# 500uH.net
KiCad netlist of a schematic drawn in EAGLE
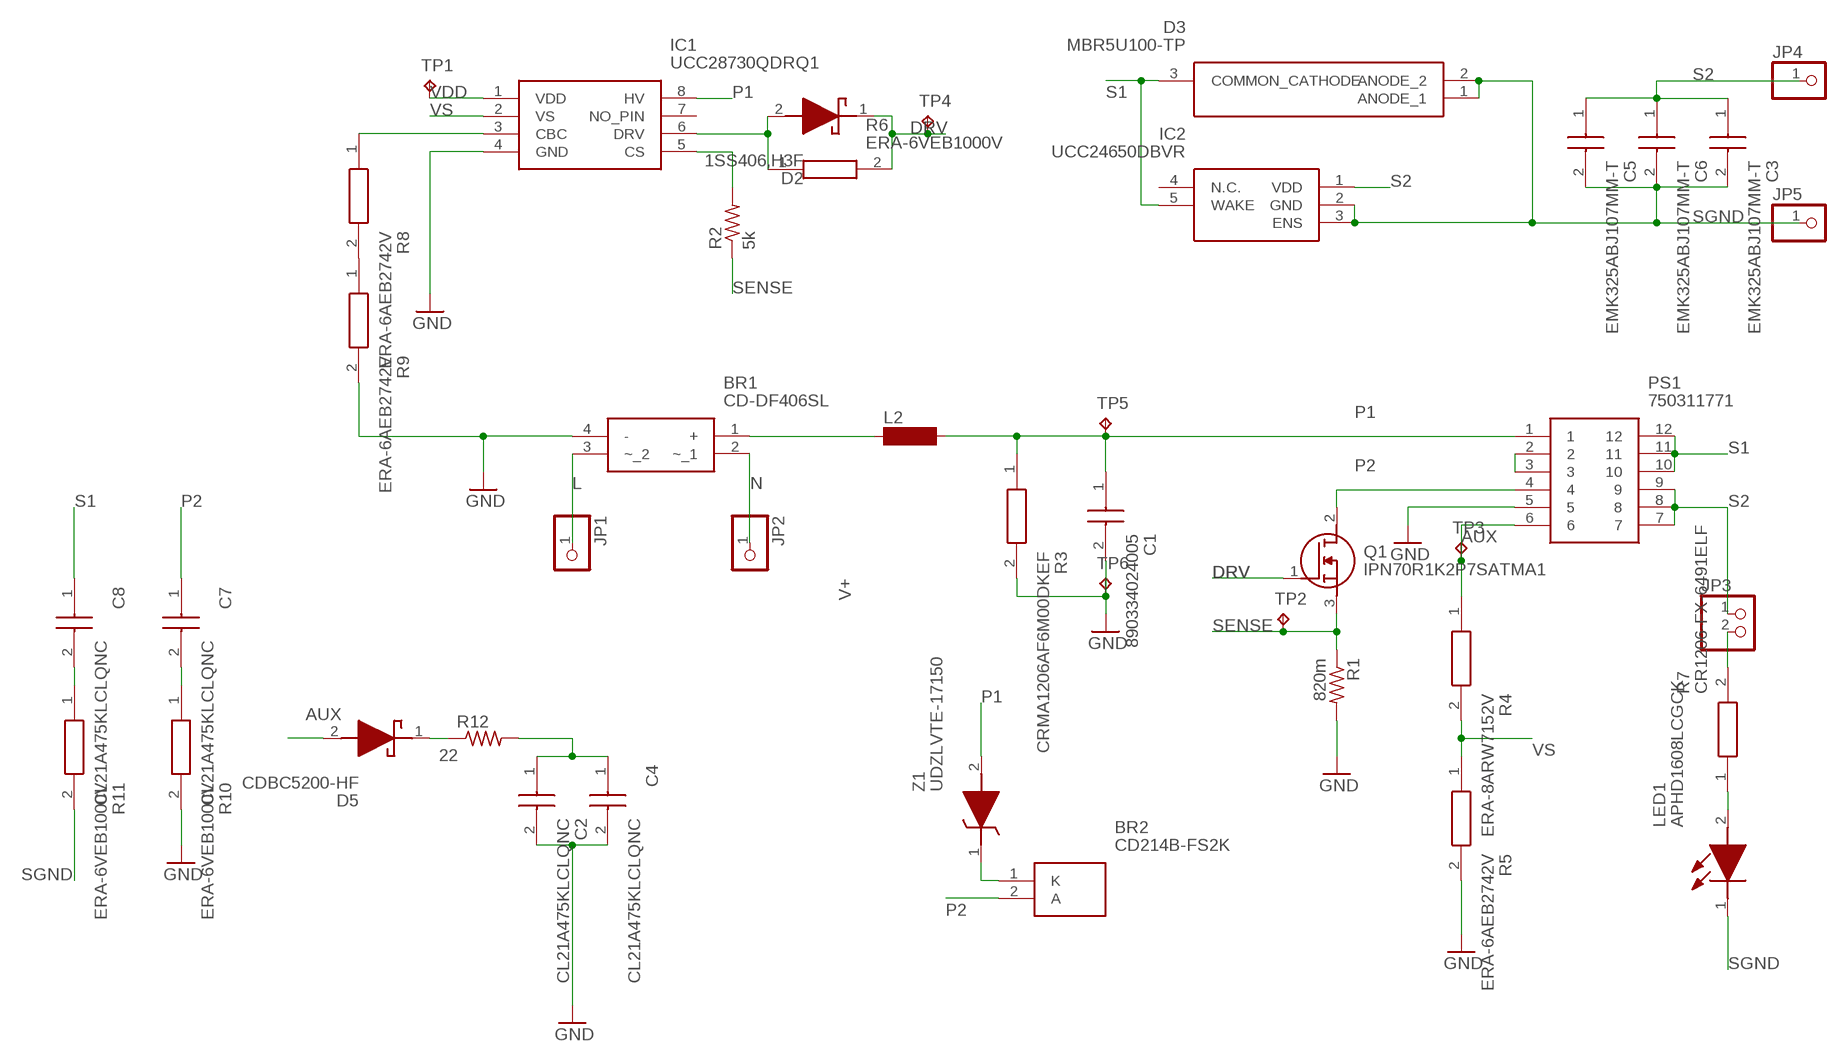
[diagram p0: schematic, sheet 1]

(export (version "E")
  (design (tool "Eeschema 10.0.6"))
  (components
    (comp (ref "BR1")
      (value "CD-DF406SL")
      (footprint "eagle-import:CDDF406SL")
      (fields (field (name "MOUSER_PART_NUMBER") "652-CD-DF406SL"))
      (libsource (lib "eagle-import") (part "CD-DF406SL"))
    )
    (comp (ref "BR2")
      (value "CD214B-FS2K")
      (footprint "eagle-import:CD214BFS2K")
      (fields (field (name "MOUSER_PART_NUMBER") "652-CD214B-FS2K"))
      (libsource (lib "eagle-import") (part "CD214B-FS2K"))
    )
    (comp (ref "C1")
      (value "890334024005")
      (footprint "eagle-import:890334024005")
      (fields (field (name "MOUSER_PART_NUMBER") "710-890334024005"))
      (libsource (lib "eagle-import") (part "890334024005"))
    )
    (comp (ref "C2")
      (value "CL21A475KLCLQNC")
      (footprint "eagle-import:CAPC2012X95N")
      (fields (field (name "MOUSER_PART_NUMBER") "187-CL21A475KLCLQNC"))
      (libsource (lib "eagle-import") (part "CL21A475KLCLQNC"))
    )
    (comp (ref "C3")
      (value "EMK325ABJ107MM-T")
      (footprint "eagle-import:CAPC3225X270N")
      (fields (field (name "MOUSER_PART_NUMBER") "963-EMK325ABJ107MM-T"))
      (libsource (lib "eagle-import") (part "EMK325ABJ107MM-T"))
    )
    (comp (ref "C4")
      (value "CL21A475KLCLQNC")
      (footprint "eagle-import:CAPC2012X95N")
      (fields (field (name "MOUSER_PART_NUMBER") "187-CL21A475KLCLQNC"))
      (libsource (lib "eagle-import") (part "CL21A475KLCLQNC"))
    )
    (comp (ref "C5")
      (value "EMK325ABJ107MM-T")
      (footprint "eagle-import:CAPC3225X270N")
      (fields (field (name "MOUSER_PART_NUMBER") "963-EMK325ABJ107MM-T"))
      (libsource (lib "eagle-import") (part "EMK325ABJ107MM-T"))
    )
    (comp (ref "C6")
      (value "EMK325ABJ107MM-T")
      (footprint "eagle-import:CAPC3225X270N")
      (fields (field (name "MOUSER_PART_NUMBER") "963-EMK325ABJ107MM-T"))
      (libsource (lib "eagle-import") (part "EMK325ABJ107MM-T"))
    )
    (comp (ref "C7")
      (value "CL21A475KLCLQNC")
      (footprint "eagle-import:CAPC2012X95N")
      (fields (field (name "MOUSER_PART_NUMBER") "187-CL21A475KLCLQNC"))
      (libsource (lib "eagle-import") (part "CL21A475KLCLQNC"))
    )
    (comp (ref "C8")
      (value "CL21A475KLCLQNC")
      (footprint "eagle-import:CAPC2012X95N")
      (fields (field (name "MOUSER_PART_NUMBER") "187-CL21A475KLCLQNC"))
      (libsource (lib "eagle-import") (part "CL21A475KLCLQNC"))
    )
    (comp (ref "D2")
      (value "1SS406,H3F")
      (footprint "eagle-import:SOD2513X115N")
      (fields (field (name "MOUSER_PART_NUMBER") "757-1SS406H3F"))
      (libsource (lib "eagle-import") (part "1SS406,H3F"))
    )
    (comp (ref "D3")
      (value "MBR5U100-TP")
      (footprint "eagle-import:MBR5U100TP")
      (libsource (lib "eagle-import") (part "MBR5U100-TP"))
    )
    (comp (ref "D5")
      (value "CDBC5200-HF")
      (footprint "eagle-import:DIOM8059X290N")
      (fields (field (name "MOUSER_PART_NUMBER") "750-CDBC5200-HF"))
      (libsource (lib "eagle-import") (part "CDBC5200-HF"))
    )
    (comp (ref "IC1")
      (value "UCC28730QDRQ1")
      (footprint "eagle-import:SOIC127P600X175-8N")
      (fields (field (name "MOUSER_PART_NUMBER") "595-UCC28730QDRQ1"))
      (libsource (lib "eagle-import") (part "UCC28730QDRQ1"))
    )
    (comp (ref "IC2")
      (value "UCC24650DBVR")
      (footprint "eagle-import:SOT95P280X145-5N")
      (fields (field (name "MOUSER_PART_NUMBER") "595-UCC24650DBVR"))
      (libsource (lib "eagle-import") (part "UCC24650DBVR"))
    )
    (comp (ref "JP1")
      (value "PINHD-1X1")
      (footprint "eagle-import:1X01")
      (libsource (lib "eagle-import") (part "PINHD-1X1"))
    )
    (comp (ref "JP2")
      (value "PINHD-1X1")
      (footprint "eagle-import:1X01")
      (libsource (lib "eagle-import") (part "PINHD-1X1"))
    )
    (comp (ref "JP3")
      (value "PINHD-1X2")
      (footprint "eagle-import:1X02")
      (libsource (lib "eagle-import") (part "PINHD-1X2"))
    )
    (comp (ref "JP4")
      (value "PINHD-1X1")
      (footprint "eagle-import:1X01")
      (libsource (lib "eagle-import") (part "PINHD-1X1"))
    )
    (comp (ref "JP5")
      (value "PINHD-1X1")
      (footprint "eagle-import:1X01")
      (libsource (lib "eagle-import") (part "PINHD-1X1"))
    )
    (comp (ref "L2")
      (value "MS50SRU1048-471Y")
      (footprint "eagle-import:INDDFN1000X1000X480-2N")
      (libsource (lib "eagle-import") (part "MS50SRU1048-471Y"))
    )
    (comp (ref "LED1")
      (value "APHD1608LCGCK")
      (footprint "eagle-import:LEDM168X80N")
      (fields (field (name "MOUSER_PART_NUMBER") "604-APHD1608LCGCK"))
      (libsource (lib "eagle-import") (part "APHD1608LCGCK"))
    )
    (comp (ref "PS1")
      (value "750311771")
      (footprint "eagle-import:750311771")
      (fields (field (name "MOUSER_PART_NUMBER") "710-750311771") (field (name "SPICEPREFIX") "X"))
      (libsource (lib "eagle-import") (part "750311771"))
    )
    (comp (ref "Q1")
      (value "IPN70R1K2P7SATMA1")
      (footprint "eagle-import:IPN70R1K2P7SATMA1")
      (fields (field (name "MOUSER_PART_NUMBER") "726-IPN70R1K2P7SATM1"))
      (libsource (lib "eagle-import") (part "IPN70R1K2P7SATMA1"))
    )
    (comp (ref "R1")
      (value "820m")
      (footprint "eagle-import:R0805")
      (libsource (lib "eagle-import") (part "R-US_R0805"))
    )
    (comp (ref "R2")
      (value "5k")
      (footprint "eagle-import:R0805")
      (libsource (lib "eagle-import") (part "R-US_R0805"))
    )
    (comp (ref "R3")
      (value "CRMA1206AF6M00DKEF")
      (footprint "eagle-import:RESC3216X74N")
      (libsource (lib "eagle-import") (part "CRMA1206AF6M00DKEF"))
    )
    (comp (ref "R4")
      (value "ERA-8ARW7152V")
      (footprint "eagle-import:ERA8A_(0805)")
      (fields (field (name "MOUSER_PART_NUMBER") "667-ERA-8ARW7152V"))
      (libsource (lib "eagle-import") (part "ERA-8ARW7152V"))
    )
    (comp (ref "R5")
      (value "ERA-6AEB2742V")
      (footprint "eagle-import:ERA6A_(0805)")
      (fields (field (name "MOUSER_PART_NUMBER") "667-ERA-6AEB2742V"))
      (libsource (lib "eagle-import") (part "ERA-6AEB2742V"))
    )
    (comp (ref "R6")
      (value "ERA-6VEB1000V")
      (footprint "eagle-import:ERA6VK")
      (fields (field (name "MOUSER_PART_NUMBER") "667-ERA-6VEB1000V"))
      (libsource (lib "eagle-import") (part "ERA-6VEB1000V"))
    )
    (comp (ref "R7")
      (value "CR1206-FX-6491ELF")
      (footprint "eagle-import:RESC3216X75N")
      (fields (field (name "MOUSER_PART_NUMBER") "652-CR1206FX-6491ELF"))
      (libsource (lib "eagle-import") (part "CR1206-FX-6491ELF"))
    )
    (comp (ref "R8")
      (value "ERA-6AEB2742V")
      (footprint "eagle-import:ERA6A_(0805)")
      (fields (field (name "MOUSER_PART_NUMBER") "667-ERA-6AEB2742V"))
      (libsource (lib "eagle-import") (part "ERA-6AEB2742V"))
    )
    (comp (ref "R9")
      (value "ERA-6AEB2742V")
      (footprint "eagle-import:ERA6A_(0805)")
      (fields (field (name "MOUSER_PART_NUMBER") "667-ERA-6AEB2742V"))
      (libsource (lib "eagle-import") (part "ERA-6AEB2742V"))
    )
    (comp (ref "R10")
      (value "ERA-6VEB1000V")
      (footprint "eagle-import:ERA6VK")
      (fields (field (name "MOUSER_PART_NUMBER") "667-ERA-6VEB1000V"))
      (libsource (lib "eagle-import") (part "ERA-6VEB1000V"))
    )
    (comp (ref "R11")
      (value "ERA-6VEB1000V")
      (footprint "eagle-import:ERA6VK")
      (fields (field (name "MOUSER_PART_NUMBER") "667-ERA-6VEB1000V"))
      (libsource (lib "eagle-import") (part "ERA-6VEB1000V"))
    )
    (comp (ref "R12")
      (value "22")
      (footprint "eagle-import:R0805")
      (libsource (lib "eagle-import") (part "R-US_R0805"))
    )
    (comp (ref "TP1")
      (value "TPB1,27")
      (footprint "eagle-import:B1,27")
      (libsource (lib "eagle-import") (part "TPB1,27"))
    )
    (comp (ref "TP2")
      (value "TPB1,27")
      (footprint "eagle-import:B1,27")
      (libsource (lib "eagle-import") (part "TPB1,27"))
    )
    (comp (ref "TP3")
      (value "TPB1,27")
      (footprint "eagle-import:B1,27")
      (libsource (lib "eagle-import") (part "TPB1,27"))
    )
    (comp (ref "TP4")
      (value "TPB1,27")
      (footprint "eagle-import:B1,27")
      (libsource (lib "eagle-import") (part "TPB1,27"))
    )
    (comp (ref "TP5")
      (value "TPB1,27")
      (footprint "eagle-import:B1,27")
      (libsource (lib "eagle-import") (part "TPB1,27"))
    )
    (comp (ref "TP6")
      (value "TPB1,27")
      (footprint "eagle-import:B1,27")
      (libsource (lib "eagle-import") (part "TPB1,27"))
    )
    (comp (ref "Z1")
      (value "UDZLVTE-17150")
      (footprint "eagle-import:SODFL2512X90N")
      (fields (field (name "MOUSER_PART_NUMBER") "755-UDZLVTE-17150"))
      (libsource (lib "eagle-import") (part "UDZLVTE-17150"))
    )
  )
  (nets
    (net (code "1") (name "/AUX") (class "Default")
      (node (ref "D5") (pin "2") (pinfunction "A_2") (pintype "bidirectional"))
      (node (ref "PS1") (pin "6") (pinfunction "6_6") (pintype "bidirectional"))
      (node (ref "R4") (pin "1") (pinfunction "1_1") (pintype "bidirectional"))
      (node (ref "TP3") (pin "TP") (pinfunction "TP_TP") (pintype "input"))
    )
    (net (code "2") (name "/DRV") (class "Default")
      (node (ref "D2") (pin "1") (pinfunction "K_1") (pintype "bidirectional"))
      (node (ref "Q1") (pin "1") (pinfunction "G_1") (pintype "bidirectional"))
      (node (ref "R6") (pin "2") (pinfunction "2_2") (pintype "bidirectional"))
      (node (ref "TP4") (pin "TP") (pinfunction "TP_TP") (pintype "input"))
    )
    (net (code "3") (name "/L") (class "Default")
      (node (ref "BR1") (pin "3") (pinfunction "~{_2}_3") (pintype "bidirectional"))
      (node (ref "JP1") (pin "1") (pinfunction "1_1") (pintype "passive"))
    )
    (net (code "4") (name "/N") (class "Default")
      (node (ref "BR1") (pin "2") (pinfunction "~{_1}_2") (pintype "bidirectional"))
      (node (ref "JP2") (pin "1") (pinfunction "1_1") (pintype "passive"))
    )
    (net (code "5") (name "/P1") (class "Default")
      (node (ref "C1") (pin "1") (pinfunction "1_1") (pintype "bidirectional"))
      (node (ref "IC1") (pin "8") (pinfunction "HV_8") (pintype "bidirectional"))
      (node (ref "L2") (pin "2") (pinfunction "2_2") (pintype "passive"))
      (node (ref "PS1") (pin "1") (pinfunction "1_1") (pintype "bidirectional"))
      (node (ref "R3") (pin "1") (pinfunction "1_1") (pintype "bidirectional"))
      (node (ref "TP5") (pin "TP") (pinfunction "TP_TP") (pintype "input"))
      (node (ref "Z1") (pin "2") (pinfunction "A_2") (pintype "bidirectional"))
    )
    (net (code "6") (name "/P2") (class "Default")
      (node (ref "BR2") (pin "2") (pinfunction "A_2") (pintype "bidirectional"))
      (node (ref "C7") (pin "1") (pinfunction "1_1") (pintype "bidirectional"))
      (node (ref "PS1") (pin "4") (pinfunction "4_4") (pintype "bidirectional"))
      (node (ref "Q1") (pin "2") (pinfunction "D_2") (pintype "bidirectional"))
    )
    (net (code "7") (name "/S1") (class "Default")
      (node (ref "C8") (pin "1") (pinfunction "1_1") (pintype "bidirectional"))
      (node (ref "D3") (pin "3") (pinfunction "COMMON_CATHODE_3") (pintype "bidirectional"))
      (node (ref "IC2") (pin "5") (pinfunction "WAKE_5") (pintype "bidirectional"))
      (node (ref "PS1") (pin "10") (pinfunction "10_10") (pintype "bidirectional"))
      (node (ref "PS1") (pin "11") (pinfunction "11_11") (pintype "bidirectional"))
      (node (ref "PS1") (pin "12") (pinfunction "12_12") (pintype "bidirectional"))
    )
    (net (code "8") (name "/S2") (class "Default")
      (node (ref "C3") (pin "1") (pinfunction "1_1") (pintype "bidirectional"))
      (node (ref "C5") (pin "1") (pinfunction "1_1") (pintype "bidirectional"))
      (node (ref "C6") (pin "1") (pinfunction "1_1") (pintype "bidirectional"))
      (node (ref "IC2") (pin "1") (pinfunction "VDD_1") (pintype "bidirectional"))
      (node (ref "JP3") (pin "1") (pinfunction "1_1") (pintype "passive"))
      (node (ref "JP4") (pin "1") (pinfunction "1_1") (pintype "passive"))
      (node (ref "PS1") (pin "7") (pinfunction "7_7") (pintype "bidirectional"))
      (node (ref "PS1") (pin "8") (pinfunction "8_8") (pintype "bidirectional"))
      (node (ref "PS1") (pin "9") (pinfunction "9_9") (pintype "bidirectional"))
    )
    (net (code "9") (name "/SENSE") (class "Default")
      (node (ref "Q1") (pin "3") (pinfunction "S_3") (pintype "bidirectional"))
      (node (ref "R1") (pin "1") (pinfunction "1_1") (pintype "passive"))
      (node (ref "R2") (pin "1") (pinfunction "1_1") (pintype "passive"))
      (node (ref "TP2") (pin "TP") (pinfunction "TP_TP") (pintype "input"))
    )
    (net (code "10") (name "/SGND") (class "Default")
      (node (ref "C3") (pin "2") (pinfunction "2_2") (pintype "bidirectional"))
      (node (ref "C5") (pin "2") (pinfunction "2_2") (pintype "bidirectional"))
      (node (ref "C6") (pin "2") (pinfunction "2_2") (pintype "bidirectional"))
      (node (ref "D3") (pin "1") (pinfunction "ANODE_1_1") (pintype "bidirectional"))
      (node (ref "D3") (pin "2") (pinfunction "ANODE_2_2") (pintype "bidirectional"))
      (node (ref "IC2") (pin "2") (pinfunction "GND_2") (pintype "bidirectional"))
      (node (ref "IC2") (pin "3") (pinfunction "ENS_3") (pintype "bidirectional"))
      (node (ref "JP5") (pin "1") (pinfunction "1_1") (pintype "passive"))
      (node (ref "LED1") (pin "1") (pinfunction "K_1") (pintype "bidirectional"))
      (node (ref "R11") (pin "2") (pinfunction "2_2") (pintype "bidirectional"))
    )
    (net (code "11") (name "/V+") (class "Default")
      (node (ref "BR1") (pin "1") (pinfunction "+_1") (pintype "bidirectional"))
      (node (ref "L2") (pin "1") (pinfunction "1_1") (pintype "passive"))
    )
    (net (code "12") (name "/VDD") (class "Default")
      (node (ref "C2") (pin "1") (pinfunction "1_1") (pintype "bidirectional"))
      (node (ref "C4") (pin "1") (pinfunction "1_1") (pintype "bidirectional"))
      (node (ref "IC1") (pin "1") (pinfunction "VDD_1") (pintype "bidirectional"))
      (node (ref "R12") (pin "2") (pinfunction "2_2") (pintype "passive"))
      (node (ref "TP1") (pin "TP") (pinfunction "TP_TP") (pintype "input"))
    )
    (net (code "13") (name "/VS") (class "Default")
      (node (ref "IC1") (pin "2") (pinfunction "VS_2") (pintype "bidirectional"))
      (node (ref "R4") (pin "2") (pinfunction "2_2") (pintype "bidirectional"))
      (node (ref "R5") (pin "1") (pinfunction "1_1") (pintype "bidirectional"))
    )
    (net (code "14") (name "GND") (class "Default")
      (node (ref "BR1") (pin "4") (pinfunction "-_4") (pintype "bidirectional"))
      (node (ref "C1") (pin "2") (pinfunction "2_2") (pintype "bidirectional"))
      (node (ref "C2") (pin "2") (pinfunction "2_2") (pintype "bidirectional"))
      (node (ref "C4") (pin "2") (pinfunction "2_2") (pintype "bidirectional"))
      (node (ref "IC1") (pin "4") (pinfunction "GND_4") (pintype "bidirectional"))
      (node (ref "PS1") (pin "5") (pinfunction "5_5") (pintype "bidirectional"))
      (node (ref "R1") (pin "2") (pinfunction "2_2") (pintype "passive"))
      (node (ref "R10") (pin "2") (pinfunction "2_2") (pintype "bidirectional"))
      (node (ref "R3") (pin "2") (pinfunction "2_2") (pintype "bidirectional"))
      (node (ref "R5") (pin "2") (pinfunction "2_2") (pintype "bidirectional"))
      (node (ref "R9") (pin "2") (pinfunction "2_2") (pintype "bidirectional"))
      (node (ref "TP6") (pin "TP") (pinfunction "TP_TP") (pintype "input"))
    )
    (net (code "15") (name "Net-(BR2-K)") (class "Default")
      (node (ref "BR2") (pin "1") (pinfunction "K_1") (pintype "bidirectional"))
      (node (ref "Z1") (pin "1") (pinfunction "K_1") (pintype "bidirectional"))
    )
    (net (code "16") (name "Net-(C7-Pad2)") (class "Default")
      (node (ref "C7") (pin "2") (pinfunction "2_2") (pintype "bidirectional"))
      (node (ref "R10") (pin "1") (pinfunction "1_1") (pintype "bidirectional"))
    )
    (net (code "17") (name "Net-(C8-Pad2)") (class "Default")
      (node (ref "C8") (pin "2") (pinfunction "2_2") (pintype "bidirectional"))
      (node (ref "R11") (pin "1") (pinfunction "1_1") (pintype "bidirectional"))
    )
    (net (code "18") (name "Net-(D2-A)") (class "Default")
      (node (ref "D2") (pin "2") (pinfunction "A_2") (pintype "bidirectional"))
      (node (ref "IC1") (pin "6") (pinfunction "DRV_6") (pintype "bidirectional"))
      (node (ref "R6") (pin "1") (pinfunction "1_1") (pintype "bidirectional"))
    )
    (net (code "19") (name "Net-(D5-K)") (class "Default")
      (node (ref "D5") (pin "1") (pinfunction "K_1") (pintype "bidirectional"))
      (node (ref "R12") (pin "1") (pinfunction "1_1") (pintype "passive"))
    )
    (net (code "20") (name "Net-(IC1-CBC)") (class "Default")
      (node (ref "IC1") (pin "3") (pinfunction "CBC_3") (pintype "bidirectional"))
      (node (ref "R8") (pin "1") (pinfunction "1_1") (pintype "bidirectional"))
    )
    (net (code "21") (name "Net-(IC1-CS)") (class "Default")
      (node (ref "IC1") (pin "5") (pinfunction "CS_5") (pintype "bidirectional"))
      (node (ref "R2") (pin "2") (pinfunction "2_2") (pintype "passive"))
    )
    (net (code "22") (name "Net-(JP3-Pad2)") (class "Default")
      (node (ref "JP3") (pin "2") (pinfunction "2_2") (pintype "passive"))
      (node (ref "R7") (pin "2") (pinfunction "2_2") (pintype "bidirectional"))
    )
    (net (code "23") (name "Net-(LED1-A)") (class "Default")
      (node (ref "LED1") (pin "2") (pinfunction "A_2") (pintype "bidirectional"))
      (node (ref "R7") (pin "1") (pinfunction "1_1") (pintype "bidirectional"))
    )
    (net (code "24") (name "Net-(PS1-Pad2)") (class "Default")
      (node (ref "PS1") (pin "2") (pinfunction "2_2") (pintype "bidirectional"))
      (node (ref "PS1") (pin "3") (pinfunction "3_3") (pintype "bidirectional"))
    )
    (net (code "25") (name "Net-(R8-Pad2)") (class "Default")
      (node (ref "R8") (pin "2") (pinfunction "2_2") (pintype "bidirectional"))
      (node (ref "R9") (pin "1") (pinfunction "1_1") (pintype "bidirectional"))
    )
    (net (code "26") (name "unconnected-(IC1-NO_PIN-Pad7)") (class "Default")
      (node (ref "IC1") (pin "7") (pinfunction "NO_PIN_7") (pintype "bidirectional"))
    )
    (net (code "27") (name "unconnected-(IC2-N.C.-Pad4)") (class "Default")
      (node (ref "IC2") (pin "4") (pinfunction "N.C._4") (pintype "no_connect"))
    )
  )
)
